# MX25R6435F_Breakout.net
KiCad netlist of a schematic drawn in EAGLE
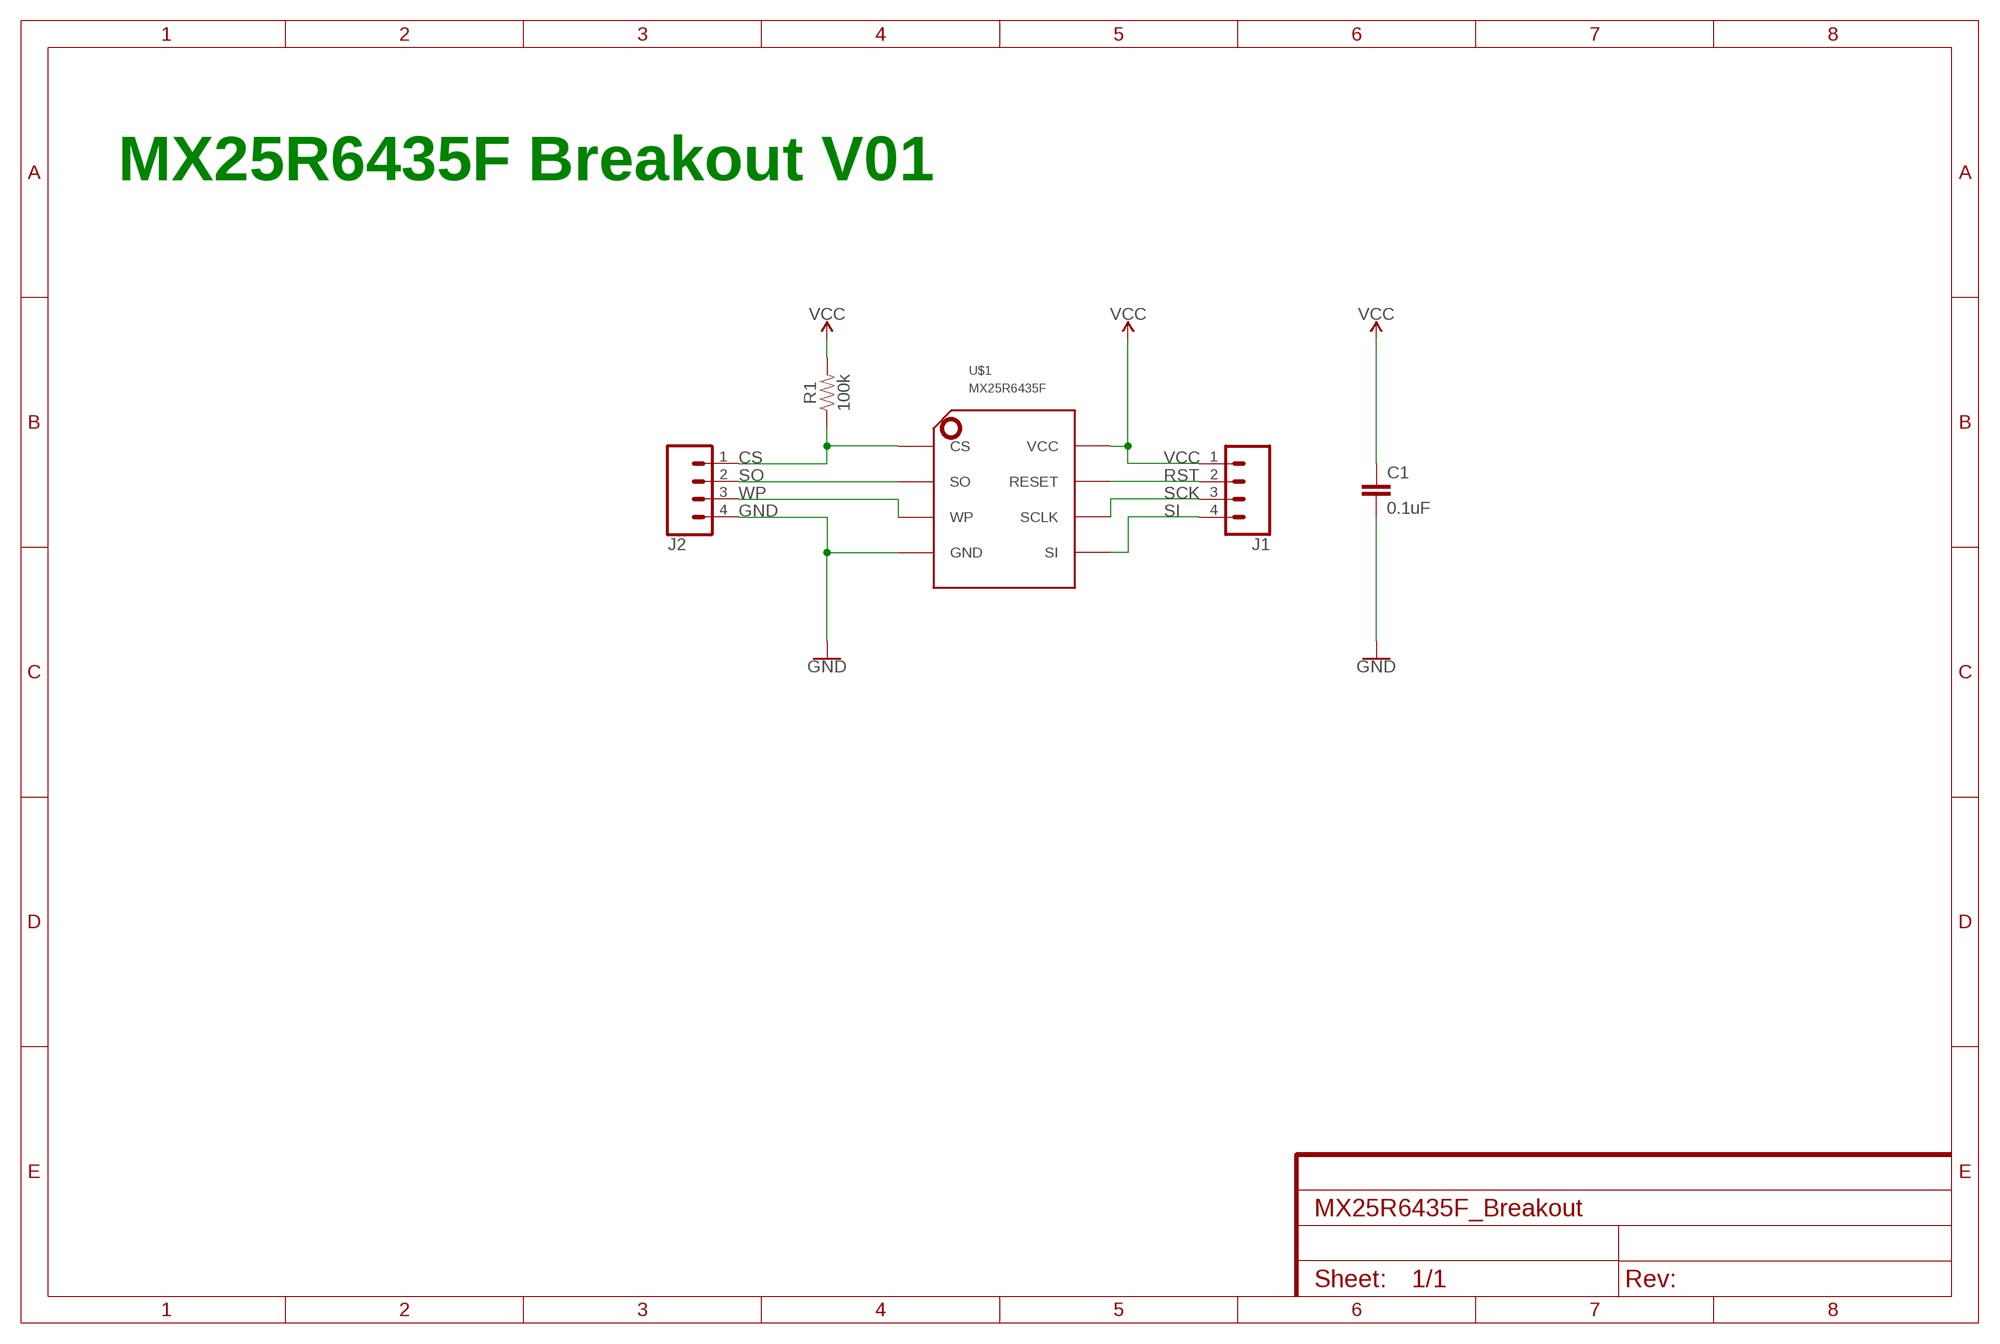
[diagram p0: schematic, sheet 1]

(export (version "E")
  (design (tool "Eeschema 10.0.6"))
  (components
    (comp (ref "C1")
      (value "0.1uF")
      (footprint "eagle-import:0603")
      (libsource (lib "eagle-import") (part "0.1UF-0603-25V-5%"))
    )
    (comp (ref "J1")
      (value "CONN_04")
      (footprint "eagle-import:1X04")
      (libsource (lib "eagle-import") (part "CONN_04"))
    )
    (comp (ref "J2")
      (value "CONN_04")
      (footprint "eagle-import:1X04")
      (libsource (lib "eagle-import") (part "CONN_04"))
    )
    (comp (ref "R1")
      (value "100k")
      (footprint "eagle-import:0603")
      (libsource (lib "eagle-import") (part "100KOHM-0603-1/10W-1%"))
    )
    (comp (ref "U$1")
      (value "MX25R6435F")
      (footprint "eagle-import:8-USON_MX25R6435F")
      (libsource (lib "eagle-import") (part "MX25R6435F"))
    )
  )
  (nets
    (net (code "1") (name "/CS") (class "Default")
      (node (ref "J2") (pin "1") (pinfunction "1_1") (pintype "passive"))
      (node (ref "R1") (pin "1") (pinfunction "1_1") (pintype "passive"))
      (node (ref "U$1") (pin "CS$1") (pinfunction "CS_CS$1") (pintype "bidirectional"))
    )
    (net (code "2") (name "/RST") (class "Default")
      (node (ref "J1") (pin "2") (pinfunction "2_2") (pintype "passive"))
      (node (ref "U$1") (pin "RESET$7") (pinfunction "RESET_RESET$7") (pintype "bidirectional"))
    )
    (net (code "3") (name "/SCK") (class "Default")
      (node (ref "J1") (pin "3") (pinfunction "3_3") (pintype "passive"))
      (node (ref "U$1") (pin "SCLK$6") (pinfunction "SCLK_SCLK$6") (pintype "bidirectional"))
    )
    (net (code "4") (name "/SI") (class "Default")
      (node (ref "J1") (pin "4") (pinfunction "4_4") (pintype "passive"))
      (node (ref "U$1") (pin "SI$5") (pinfunction "SI_SI$5") (pintype "bidirectional"))
    )
    (net (code "5") (name "/SO") (class "Default")
      (node (ref "J2") (pin "2") (pinfunction "2_2") (pintype "passive"))
      (node (ref "U$1") (pin "SO$2") (pinfunction "SO_SO$2") (pintype "bidirectional"))
    )
    (net (code "6") (name "/WP") (class "Default")
      (node (ref "J2") (pin "3") (pinfunction "3_3") (pintype "passive"))
      (node (ref "U$1") (pin "WP$3") (pinfunction "WP_WP$3") (pintype "bidirectional"))
    )
    (net (code "7") (name "GND") (class "Default")
      (node (ref "C1") (pin "2") (pinfunction "2_2") (pintype "passive"))
      (node (ref "J2") (pin "4") (pinfunction "4_4") (pintype "passive"))
      (node (ref "U$1") (pin "GND$4") (pinfunction "GND_GND$4") (pintype "bidirectional"))
    )
    (net (code "8") (name "VCC") (class "Default")
      (node (ref "C1") (pin "1") (pinfunction "1_1") (pintype "passive"))
      (node (ref "J1") (pin "1") (pinfunction "1_1") (pintype "passive"))
      (node (ref "R1") (pin "2") (pinfunction "2_2") (pintype "passive"))
      (node (ref "U$1") (pin "VCC$8") (pinfunction "VCC_VCC$8") (pintype "bidirectional"))
    )
  )
)
